# chrg_station.net
KiCad netlist of a schematic drawn in Altium Designer
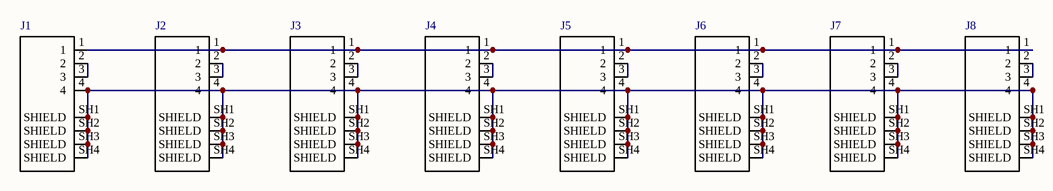
[diagram p0: chrg_station.SchDoc]

(export (version "E")
  (design (tool "Eeschema 10.0.6"))
  (components
    (comp (ref "J1")
      (value "292336-1")
      (footprint "*TE_292336-1_292336-1(Primary)")
      (description "Connector USB Receptacle 4 Position 2mm Solder Right Angle Thru-Hole 4 Terminal 1 Port Tube")
      (fields (field (name "MF") "TE Connectivity"))
      (libsource (lib "292336-1") (part "292336-1"))
    )
    (comp (ref "J2")
      (value "292336-1")
      (footprint "*TE_292336-1_292336-1(Primary)")
      (description "Connector USB Receptacle 4 Position 2mm Solder Right Angle Thru-Hole 4 Terminal 1 Port Tube")
      (fields (field (name "MF") "TE Connectivity"))
      (libsource (lib "292336-1") (part "292336-1"))
    )
    (comp (ref "J3")
      (value "292336-1")
      (footprint "*TE_292336-1_292336-1(Primary)")
      (description "Connector USB Receptacle 4 Position 2mm Solder Right Angle Thru-Hole 4 Terminal 1 Port Tube")
      (fields (field (name "MF") "TE Connectivity"))
      (libsource (lib "292336-1") (part "292336-1"))
    )
    (comp (ref "J4")
      (value "292336-1")
      (footprint "*TE_292336-1_292336-1(Primary)")
      (description "Connector USB Receptacle 4 Position 2mm Solder Right Angle Thru-Hole 4 Terminal 1 Port Tube")
      (fields (field (name "MF") "TE Connectivity"))
      (libsource (lib "292336-1") (part "292336-1"))
    )
    (comp (ref "J5")
      (value "292336-1")
      (footprint "*TE_292336-1_292336-1(Primary)")
      (description "Connector USB Receptacle 4 Position 2mm Solder Right Angle Thru-Hole 4 Terminal 1 Port Tube")
      (fields (field (name "MF") "TE Connectivity"))
      (libsource (lib "292336-1") (part "292336-1"))
    )
    (comp (ref "J6")
      (value "292336-1")
      (footprint "*TE_292336-1_292336-1(Primary)")
      (description "Connector USB Receptacle 4 Position 2mm Solder Right Angle Thru-Hole 4 Terminal 1 Port Tube")
      (fields (field (name "MF") "TE Connectivity"))
      (libsource (lib "292336-1") (part "292336-1"))
    )
    (comp (ref "J7")
      (value "292336-1")
      (footprint "*TE_292336-1_292336-1(Primary)")
      (description "Connector USB Receptacle 4 Position 2mm Solder Right Angle Thru-Hole 4 Terminal 1 Port Tube")
      (fields (field (name "MF") "TE Connectivity"))
      (libsource (lib "292336-1") (part "292336-1"))
    )
    (comp (ref "J8")
      (value "292336-1")
      (footprint "*TE_292336-1_292336-1(Primary)")
      (description "Connector USB Receptacle 4 Position 2mm Solder Right Angle Thru-Hole 4 Terminal 1 Port Tube")
      (fields (field (name "MF") "TE Connectivity"))
      (libsource (lib "292336-1") (part "292336-1"))
    )
  )
  (nets
    (net (code "1") (name "Net-(J1-Pad1)") (class "Default")
      (node (ref "J1") (pin "1") (pinfunction "1_1") (pintype "passive"))
      (node (ref "J2") (pin "1") (pinfunction "1_1") (pintype "passive"))
      (node (ref "J3") (pin "1") (pinfunction "1_1") (pintype "passive"))
      (node (ref "J4") (pin "1") (pinfunction "1_1") (pintype "passive"))
      (node (ref "J5") (pin "1") (pinfunction "1_1") (pintype "passive"))
      (node (ref "J6") (pin "1") (pinfunction "1_1") (pintype "passive"))
      (node (ref "J7") (pin "1") (pinfunction "1_1") (pintype "passive"))
      (node (ref "J8") (pin "1") (pinfunction "1_1") (pintype "passive"))
    )
    (net (code "2") (name "Net-(J1-Pad2)") (class "Default")
      (node (ref "J1") (pin "2") (pinfunction "2_2") (pintype "passive"))
      (node (ref "J1") (pin "3") (pinfunction "3_3") (pintype "passive"))
    )
    (net (code "3") (name "Net-(J1-Pad4)") (class "Default")
      (node (ref "J1") (pin "4") (pinfunction "4_4") (pintype "passive"))
      (node (ref "J1") (pin "SH1") (pinfunction "SHIELD_SH1") (pintype "passive"))
      (node (ref "J1") (pin "SH2") (pinfunction "SHIELD_SH2") (pintype "passive"))
      (node (ref "J1") (pin "SH3") (pinfunction "SHIELD_SH3") (pintype "passive"))
      (node (ref "J1") (pin "SH4") (pinfunction "SHIELD_SH4") (pintype "passive"))
      (node (ref "J2") (pin "4") (pinfunction "4_4") (pintype "passive"))
      (node (ref "J2") (pin "SH1") (pinfunction "SHIELD_SH1") (pintype "passive"))
      (node (ref "J2") (pin "SH2") (pinfunction "SHIELD_SH2") (pintype "passive"))
      (node (ref "J2") (pin "SH3") (pinfunction "SHIELD_SH3") (pintype "passive"))
      (node (ref "J2") (pin "SH4") (pinfunction "SHIELD_SH4") (pintype "passive"))
      (node (ref "J3") (pin "4") (pinfunction "4_4") (pintype "passive"))
      (node (ref "J3") (pin "SH1") (pinfunction "SHIELD_SH1") (pintype "passive"))
      (node (ref "J3") (pin "SH2") (pinfunction "SHIELD_SH2") (pintype "passive"))
      (node (ref "J3") (pin "SH3") (pinfunction "SHIELD_SH3") (pintype "passive"))
      (node (ref "J3") (pin "SH4") (pinfunction "SHIELD_SH4") (pintype "passive"))
      (node (ref "J4") (pin "4") (pinfunction "4_4") (pintype "passive"))
      (node (ref "J4") (pin "SH1") (pinfunction "SHIELD_SH1") (pintype "passive"))
      (node (ref "J4") (pin "SH2") (pinfunction "SHIELD_SH2") (pintype "passive"))
      (node (ref "J4") (pin "SH3") (pinfunction "SHIELD_SH3") (pintype "passive"))
      (node (ref "J4") (pin "SH4") (pinfunction "SHIELD_SH4") (pintype "passive"))
      (node (ref "J5") (pin "4") (pinfunction "4_4") (pintype "passive"))
      (node (ref "J5") (pin "SH1") (pinfunction "SHIELD_SH1") (pintype "passive"))
      (node (ref "J5") (pin "SH2") (pinfunction "SHIELD_SH2") (pintype "passive"))
      (node (ref "J5") (pin "SH3") (pinfunction "SHIELD_SH3") (pintype "passive"))
      (node (ref "J5") (pin "SH4") (pinfunction "SHIELD_SH4") (pintype "passive"))
      (node (ref "J6") (pin "4") (pinfunction "4_4") (pintype "passive"))
      (node (ref "J6") (pin "SH1") (pinfunction "SHIELD_SH1") (pintype "passive"))
      (node (ref "J6") (pin "SH2") (pinfunction "SHIELD_SH2") (pintype "passive"))
      (node (ref "J6") (pin "SH3") (pinfunction "SHIELD_SH3") (pintype "passive"))
      (node (ref "J6") (pin "SH4") (pinfunction "SHIELD_SH4") (pintype "passive"))
      (node (ref "J7") (pin "4") (pinfunction "4_4") (pintype "passive"))
      (node (ref "J7") (pin "SH1") (pinfunction "SHIELD_SH1") (pintype "passive"))
      (node (ref "J7") (pin "SH2") (pinfunction "SHIELD_SH2") (pintype "passive"))
      (node (ref "J7") (pin "SH3") (pinfunction "SHIELD_SH3") (pintype "passive"))
      (node (ref "J7") (pin "SH4") (pinfunction "SHIELD_SH4") (pintype "passive"))
      (node (ref "J8") (pin "4") (pinfunction "4_4") (pintype "passive"))
      (node (ref "J8") (pin "SH1") (pinfunction "SHIELD_SH1") (pintype "passive"))
      (node (ref "J8") (pin "SH2") (pinfunction "SHIELD_SH2") (pintype "passive"))
      (node (ref "J8") (pin "SH3") (pinfunction "SHIELD_SH3") (pintype "passive"))
      (node (ref "J8") (pin "SH4") (pinfunction "SHIELD_SH4") (pintype "passive"))
    )
    (net (code "4") (name "Net-(J2-Pad2)") (class "Default")
      (node (ref "J2") (pin "2") (pinfunction "2_2") (pintype "passive"))
      (node (ref "J2") (pin "3") (pinfunction "3_3") (pintype "passive"))
    )
    (net (code "5") (name "Net-(J3-Pad2)") (class "Default")
      (node (ref "J3") (pin "2") (pinfunction "2_2") (pintype "passive"))
      (node (ref "J3") (pin "3") (pinfunction "3_3") (pintype "passive"))
    )
    (net (code "6") (name "Net-(J4-Pad2)") (class "Default")
      (node (ref "J4") (pin "2") (pinfunction "2_2") (pintype "passive"))
      (node (ref "J4") (pin "3") (pinfunction "3_3") (pintype "passive"))
    )
    (net (code "7") (name "Net-(J5-Pad2)") (class "Default")
      (node (ref "J5") (pin "2") (pinfunction "2_2") (pintype "passive"))
      (node (ref "J5") (pin "3") (pinfunction "3_3") (pintype "passive"))
    )
    (net (code "8") (name "Net-(J6-Pad2)") (class "Default")
      (node (ref "J6") (pin "2") (pinfunction "2_2") (pintype "passive"))
      (node (ref "J6") (pin "3") (pinfunction "3_3") (pintype "passive"))
    )
    (net (code "9") (name "Net-(J7-Pad2)") (class "Default")
      (node (ref "J7") (pin "2") (pinfunction "2_2") (pintype "passive"))
      (node (ref "J7") (pin "3") (pinfunction "3_3") (pintype "passive"))
    )
    (net (code "10") (name "Net-(J8-Pad2)") (class "Default")
      (node (ref "J8") (pin "2") (pinfunction "2_2") (pintype "passive"))
      (node (ref "J8") (pin "3") (pinfunction "3_3") (pintype "passive"))
    )
  )
)
